# merch-hat.net
KiCad netlist of a schematic drawn in EAGLE
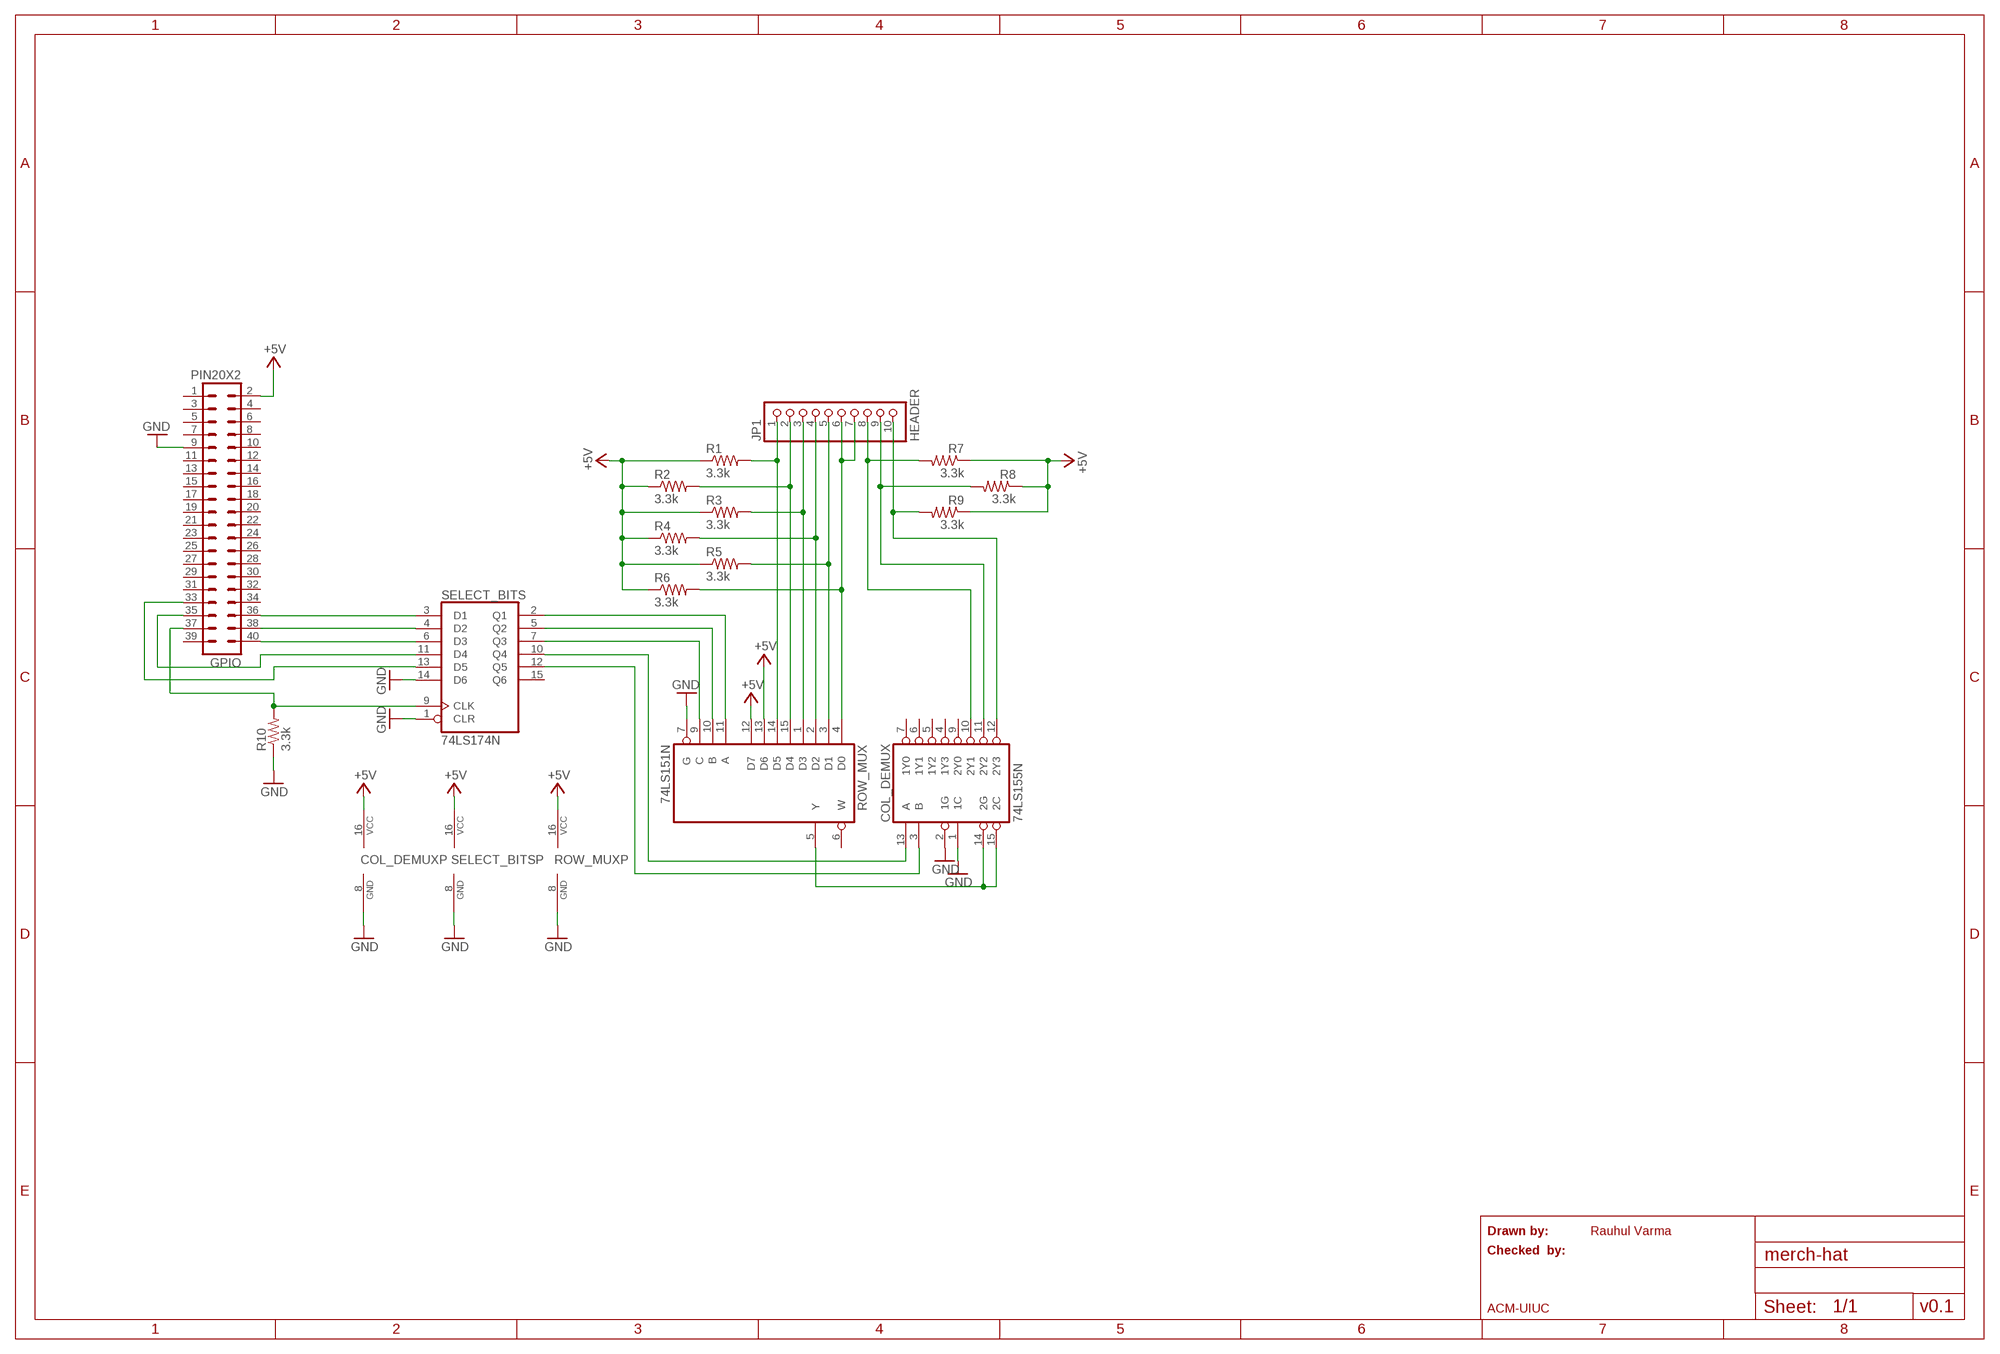
[diagram p0: schematic, sheet 1]

(export (version "E")
  (design (tool "Eeschema 10.0.6"))
  (components
    (comp (ref "COL_DEMUX")
      (value "74LS155N")
      (footprint "eagle-import:DIL16")
      (libsource (lib "eagle-import") (part "74155NLS"))
    )
    (comp (ref "GPIO")
      (value "PIN20X2")
      (footprint "eagle-import:PIN_20X2")
      (libsource (lib "eagle-import") (part "PIN20X2"))
    )
    (comp (ref "JP1")
      (value "HEADER")
      (footprint "eagle-import:1X10")
      (libsource (lib "eagle-import") (part "PINHD-1X10"))
    )
    (comp (ref "R1")
      (value "3.3k")
      (footprint "eagle-import:0207_10")
      (libsource (lib "eagle-import") (part "R-US_0207/10"))
    )
    (comp (ref "R2")
      (value "3.3k")
      (footprint "eagle-import:0207_10")
      (libsource (lib "eagle-import") (part "R-US_0207/10"))
    )
    (comp (ref "R3")
      (value "3.3k")
      (footprint "eagle-import:0207_10")
      (libsource (lib "eagle-import") (part "R-US_0207/10"))
    )
    (comp (ref "R4")
      (value "3.3k")
      (footprint "eagle-import:0207_10")
      (libsource (lib "eagle-import") (part "R-US_0207/10"))
    )
    (comp (ref "R5")
      (value "3.3k")
      (footprint "eagle-import:0207_10")
      (libsource (lib "eagle-import") (part "R-US_0207/10"))
    )
    (comp (ref "R6")
      (value "3.3k")
      (footprint "eagle-import:0207_10")
      (libsource (lib "eagle-import") (part "R-US_0207/10"))
    )
    (comp (ref "R7")
      (value "3.3k")
      (footprint "eagle-import:0207_10")
      (libsource (lib "eagle-import") (part "R-US_0207/10"))
    )
    (comp (ref "R8")
      (value "3.3k")
      (footprint "eagle-import:0207_10")
      (libsource (lib "eagle-import") (part "R-US_0207/10"))
    )
    (comp (ref "R9")
      (value "3.3k")
      (footprint "eagle-import:0207_10")
      (libsource (lib "eagle-import") (part "R-US_0207/10"))
    )
    (comp (ref "R10")
      (value "3.3k")
      (footprint "eagle-import:0207_10")
      (libsource (lib "eagle-import") (part "R-US_0207/10"))
    )
    (comp (ref "ROW_MUX")
      (value "74LS151N")
      (footprint "eagle-import:DIL16")
      (libsource (lib "eagle-import") (part "74151NLS"))
    )
    (comp (ref "SELECT_BITS")
      (value "74LS174N")
      (footprint "eagle-import:DIL16")
      (libsource (lib "eagle-import") (part "74174NLS"))
    )
  )
  (nets
    (net (code "1") (name "+5V") (class "Default")
      (node (ref "COL_DEMUX") (pin "16") (pinfunction "VCC_16") (pintype "power_in"))
      (node (ref "GPIO") (pin "2") (pinfunction "2_2") (pintype "passive"))
      (node (ref "R1") (pin "1") (pinfunction "1_1") (pintype "passive"))
      (node (ref "R2") (pin "1") (pinfunction "1_1") (pintype "passive"))
      (node (ref "R3") (pin "1") (pinfunction "1_1") (pintype "passive"))
      (node (ref "R4") (pin "1") (pinfunction "1_1") (pintype "passive"))
      (node (ref "R5") (pin "1") (pinfunction "1_1") (pintype "passive"))
      (node (ref "R6") (pin "1") (pinfunction "1_1") (pintype "passive"))
      (node (ref "R7") (pin "1") (pinfunction "1_1") (pintype "passive"))
      (node (ref "R8") (pin "1") (pinfunction "1_1") (pintype "passive"))
      (node (ref "R9") (pin "1") (pinfunction "1_1") (pintype "passive"))
      (node (ref "ROW_MUX") (pin "12") (pinfunction "D7_12") (pintype "input"))
      (node (ref "ROW_MUX") (pin "13") (pinfunction "D6_13") (pintype "input"))
      (node (ref "ROW_MUX") (pin "16") (pinfunction "VCC_16") (pintype "power_in"))
      (node (ref "SELECT_BITS") (pin "16") (pinfunction "VCC_16") (pintype "power_in"))
    )
    (net (code "2") (name "GND") (class "Default")
      (node (ref "COL_DEMUX") (pin "1") (pinfunction "1C_1") (pintype "input"))
      (node (ref "COL_DEMUX") (pin "2") (pinfunction "1G_2") (pintype "input"))
      (node (ref "COL_DEMUX") (pin "8") (pinfunction "GND_8") (pintype "power_in"))
      (node (ref "GPIO") (pin "9") (pinfunction "9_9") (pintype "passive"))
      (node (ref "R10") (pin "1") (pinfunction "1_1") (pintype "passive"))
      (node (ref "ROW_MUX") (pin "7") (pinfunction "G_7") (pintype "input"))
      (node (ref "ROW_MUX") (pin "8") (pinfunction "GND_8") (pintype "power_in"))
      (node (ref "SELECT_BITS") (pin "1") (pinfunction "CLR_1") (pintype "input"))
      (node (ref "SELECT_BITS") (pin "14") (pinfunction "D6_14") (pintype "input"))
      (node (ref "SELECT_BITS") (pin "8") (pinfunction "GND_8") (pintype "power_in"))
    )
    (net (code "3") (name "Net-(COL_DEMUXA-2C)") (class "Default")
      (node (ref "COL_DEMUX") (pin "14") (pinfunction "2G_14") (pintype "input"))
      (node (ref "COL_DEMUX") (pin "15") (pinfunction "2C_15") (pintype "input"))
      (node (ref "ROW_MUX") (pin "5") (pinfunction "Y_5") (pintype "output"))
    )
    (net (code "4") (name "Net-(COL_DEMUXA-2Y1)") (class "Default")
      (node (ref "COL_DEMUX") (pin "10") (pinfunction "2Y1_10") (pintype "output"))
      (node (ref "JP1") (pin "8") (pinfunction "8_8") (pintype "passive"))
      (node (ref "R7") (pin "2") (pinfunction "2_2") (pintype "passive"))
    )
    (net (code "5") (name "Net-(COL_DEMUXA-2Y2)") (class "Default")
      (node (ref "COL_DEMUX") (pin "11") (pinfunction "2Y2_11") (pintype "output"))
      (node (ref "JP1") (pin "9") (pinfunction "9_9") (pintype "passive"))
      (node (ref "R8") (pin "2") (pinfunction "2_2") (pintype "passive"))
    )
    (net (code "6") (name "Net-(COL_DEMUXA-2Y3)") (class "Default")
      (node (ref "COL_DEMUX") (pin "12") (pinfunction "2Y3_12") (pintype "output"))
      (node (ref "JP1") (pin "10") (pinfunction "10_10") (pintype "passive"))
      (node (ref "R9") (pin "2") (pinfunction "2_2") (pintype "passive"))
    )
    (net (code "7") (name "Net-(COL_DEMUXA-A)") (class "Default")
      (node (ref "COL_DEMUX") (pin "13") (pinfunction "A_13") (pintype "input"))
      (node (ref "SELECT_BITS") (pin "10") (pinfunction "Q4_10") (pintype "output"))
    )
    (net (code "8") (name "Net-(COL_DEMUXA-B)") (class "Default")
      (node (ref "COL_DEMUX") (pin "3") (pinfunction "B_3") (pintype "input"))
      (node (ref "SELECT_BITS") (pin "12") (pinfunction "Q5_12") (pintype "output"))
    )
    (net (code "9") (name "Net-(ROW_MUXA-A)") (class "Default")
      (node (ref "ROW_MUX") (pin "11") (pinfunction "A_11") (pintype "input"))
      (node (ref "SELECT_BITS") (pin "2") (pinfunction "Q1_2") (pintype "output"))
    )
    (net (code "10") (name "Net-(ROW_MUXA-B)") (class "Default")
      (node (ref "ROW_MUX") (pin "10") (pinfunction "B_10") (pintype "input"))
      (node (ref "SELECT_BITS") (pin "5") (pinfunction "Q2_5") (pintype "output"))
    )
    (net (code "11") (name "Net-(ROW_MUXA-C)") (class "Default")
      (node (ref "ROW_MUX") (pin "9") (pinfunction "C_9") (pintype "input"))
      (node (ref "SELECT_BITS") (pin "7") (pinfunction "Q3_7") (pintype "output"))
    )
    (net (code "12") (name "Net-(ROW_MUXA-D0)") (class "Default")
      (node (ref "JP1") (pin "6") (pinfunction "6_6") (pintype "passive"))
      (node (ref "JP1") (pin "7") (pinfunction "7_7") (pintype "passive"))
      (node (ref "R6") (pin "2") (pinfunction "2_2") (pintype "passive"))
      (node (ref "ROW_MUX") (pin "4") (pinfunction "D0_4") (pintype "input"))
    )
    (net (code "13") (name "Net-(ROW_MUXA-D1)") (class "Default")
      (node (ref "JP1") (pin "5") (pinfunction "5_5") (pintype "passive"))
      (node (ref "R5") (pin "2") (pinfunction "2_2") (pintype "passive"))
      (node (ref "ROW_MUX") (pin "3") (pinfunction "D1_3") (pintype "input"))
    )
    (net (code "14") (name "Net-(ROW_MUXA-D2)") (class "Default")
      (node (ref "JP1") (pin "4") (pinfunction "4_4") (pintype "passive"))
      (node (ref "R4") (pin "2") (pinfunction "2_2") (pintype "passive"))
      (node (ref "ROW_MUX") (pin "2") (pinfunction "D2_2") (pintype "input"))
    )
    (net (code "15") (name "Net-(ROW_MUXA-D3)") (class "Default")
      (node (ref "JP1") (pin "3") (pinfunction "3_3") (pintype "passive"))
      (node (ref "R3") (pin "2") (pinfunction "2_2") (pintype "passive"))
      (node (ref "ROW_MUX") (pin "1") (pinfunction "D3_1") (pintype "input"))
    )
    (net (code "16") (name "Net-(ROW_MUXA-D4)") (class "Default")
      (node (ref "JP1") (pin "2") (pinfunction "2_2") (pintype "passive"))
      (node (ref "R2") (pin "2") (pinfunction "2_2") (pintype "passive"))
      (node (ref "ROW_MUX") (pin "15") (pinfunction "D4_15") (pintype "input"))
    )
    (net (code "17") (name "Net-(ROW_MUXA-D5)") (class "Default")
      (node (ref "JP1") (pin "1") (pinfunction "1_1") (pintype "passive"))
      (node (ref "R1") (pin "2") (pinfunction "2_2") (pintype "passive"))
      (node (ref "ROW_MUX") (pin "14") (pinfunction "D5_14") (pintype "input"))
    )
    (net (code "18") (name "Net-(SELECT_BITSA-CLK)") (class "Default")
      (node (ref "GPIO") (pin "37") (pinfunction "37_37") (pintype "passive"))
      (node (ref "R10") (pin "2") (pinfunction "2_2") (pintype "passive"))
      (node (ref "SELECT_BITS") (pin "9") (pinfunction "CLK_9") (pintype "input"))
    )
    (net (code "19") (name "Net-(SELECT_BITSA-D1)") (class "Default")
      (node (ref "GPIO") (pin "36") (pinfunction "36_36") (pintype "passive"))
      (node (ref "SELECT_BITS") (pin "3") (pinfunction "D1_3") (pintype "input"))
    )
    (net (code "20") (name "Net-(SELECT_BITSA-D2)") (class "Default")
      (node (ref "GPIO") (pin "38") (pinfunction "38_38") (pintype "passive"))
      (node (ref "SELECT_BITS") (pin "4") (pinfunction "D2_4") (pintype "input"))
    )
    (net (code "21") (name "Net-(SELECT_BITSA-D3)") (class "Default")
      (node (ref "GPIO") (pin "40") (pinfunction "40_40") (pintype "passive"))
      (node (ref "SELECT_BITS") (pin "6") (pinfunction "D3_6") (pintype "input"))
    )
    (net (code "22") (name "Net-(SELECT_BITSA-D4)") (class "Default")
      (node (ref "GPIO") (pin "35") (pinfunction "35_35") (pintype "passive"))
      (node (ref "SELECT_BITS") (pin "11") (pinfunction "D4_11") (pintype "input"))
    )
    (net (code "23") (name "Net-(SELECT_BITSA-D5)") (class "Default")
      (node (ref "GPIO") (pin "33") (pinfunction "33_33") (pintype "passive"))
      (node (ref "SELECT_BITS") (pin "13") (pinfunction "D5_13") (pintype "input"))
    )
    (net (code "24") (name "unconnected-(COL_DEMUXA-1Y0-Pad7)") (class "Default")
      (node (ref "COL_DEMUX") (pin "7") (pinfunction "1Y0_7") (pintype "output"))
    )
    (net (code "25") (name "unconnected-(COL_DEMUXA-1Y1-Pad6)") (class "Default")
      (node (ref "COL_DEMUX") (pin "6") (pinfunction "1Y1_6") (pintype "output"))
    )
    (net (code "26") (name "unconnected-(COL_DEMUXA-1Y2-Pad5)") (class "Default")
      (node (ref "COL_DEMUX") (pin "5") (pinfunction "1Y2_5") (pintype "output"))
    )
    (net (code "27") (name "unconnected-(COL_DEMUXA-1Y3-Pad4)") (class "Default")
      (node (ref "COL_DEMUX") (pin "4") (pinfunction "1Y3_4") (pintype "output"))
    )
    (net (code "28") (name "unconnected-(COL_DEMUXA-2Y0-Pad9)") (class "Default")
      (node (ref "COL_DEMUX") (pin "9") (pinfunction "2Y0_9") (pintype "output"))
    )
    (net (code "29") (name "unconnected-(GPIO-Pad1)") (class "Default")
      (node (ref "GPIO") (pin "1") (pinfunction "1_1") (pintype "passive"))
    )
    (net (code "30") (name "unconnected-(GPIO-Pad3)") (class "Default")
      (node (ref "GPIO") (pin "3") (pinfunction "3_3") (pintype "passive"))
    )
    (net (code "31") (name "unconnected-(GPIO-Pad4)") (class "Default")
      (node (ref "GPIO") (pin "4") (pinfunction "4_4") (pintype "passive"))
    )
    (net (code "32") (name "unconnected-(GPIO-Pad5)") (class "Default")
      (node (ref "GPIO") (pin "5") (pinfunction "5_5") (pintype "passive"))
    )
    (net (code "33") (name "unconnected-(GPIO-Pad6)") (class "Default")
      (node (ref "GPIO") (pin "6") (pinfunction "6_6") (pintype "passive"))
    )
    (net (code "34") (name "unconnected-(GPIO-Pad7)") (class "Default")
      (node (ref "GPIO") (pin "7") (pinfunction "7_7") (pintype "passive"))
    )
    (net (code "35") (name "unconnected-(GPIO-Pad8)") (class "Default")
      (node (ref "GPIO") (pin "8") (pinfunction "8_8") (pintype "passive"))
    )
    (net (code "36") (name "unconnected-(GPIO-Pad10)") (class "Default")
      (node (ref "GPIO") (pin "10") (pinfunction "10_10") (pintype "passive"))
    )
    (net (code "37") (name "unconnected-(GPIO-Pad11)") (class "Default")
      (node (ref "GPIO") (pin "11") (pinfunction "11_11") (pintype "passive"))
    )
    (net (code "38") (name "unconnected-(GPIO-Pad12)") (class "Default")
      (node (ref "GPIO") (pin "12") (pinfunction "12_12") (pintype "passive"))
    )
    (net (code "39") (name "unconnected-(GPIO-Pad13)") (class "Default")
      (node (ref "GPIO") (pin "13") (pinfunction "13_13") (pintype "passive"))
    )
    (net (code "40") (name "unconnected-(GPIO-Pad14)") (class "Default")
      (node (ref "GPIO") (pin "14") (pinfunction "14_14") (pintype "passive"))
    )
    (net (code "41") (name "unconnected-(GPIO-Pad15)") (class "Default")
      (node (ref "GPIO") (pin "15") (pinfunction "15_15") (pintype "passive"))
    )
    (net (code "42") (name "unconnected-(GPIO-Pad16)") (class "Default")
      (node (ref "GPIO") (pin "16") (pinfunction "16_16") (pintype "passive"))
    )
    (net (code "43") (name "unconnected-(GPIO-Pad17)") (class "Default")
      (node (ref "GPIO") (pin "17") (pinfunction "17_17") (pintype "passive"))
    )
    (net (code "44") (name "unconnected-(GPIO-Pad18)") (class "Default")
      (node (ref "GPIO") (pin "18") (pinfunction "18_18") (pintype "passive"))
    )
    (net (code "45") (name "unconnected-(GPIO-Pad19)") (class "Default")
      (node (ref "GPIO") (pin "19") (pinfunction "19_19") (pintype "passive"))
    )
    (net (code "46") (name "unconnected-(GPIO-Pad20)") (class "Default")
      (node (ref "GPIO") (pin "20") (pinfunction "20_20") (pintype "passive"))
    )
    (net (code "47") (name "unconnected-(GPIO-Pad21)") (class "Default")
      (node (ref "GPIO") (pin "21") (pinfunction "21_21") (pintype "passive"))
    )
    (net (code "48") (name "unconnected-(GPIO-Pad22)") (class "Default")
      (node (ref "GPIO") (pin "22") (pinfunction "22_22") (pintype "passive"))
    )
    (net (code "49") (name "unconnected-(GPIO-Pad23)") (class "Default")
      (node (ref "GPIO") (pin "23") (pinfunction "23_23") (pintype "passive"))
    )
    (net (code "50") (name "unconnected-(GPIO-Pad24)") (class "Default")
      (node (ref "GPIO") (pin "24") (pinfunction "24_24") (pintype "passive"))
    )
    (net (code "51") (name "unconnected-(GPIO-Pad25)") (class "Default")
      (node (ref "GPIO") (pin "25") (pinfunction "25_25") (pintype "passive"))
    )
    (net (code "52") (name "unconnected-(GPIO-Pad26)") (class "Default")
      (node (ref "GPIO") (pin "26") (pinfunction "26_26") (pintype "passive"))
    )
    (net (code "53") (name "unconnected-(GPIO-Pad27)") (class "Default")
      (node (ref "GPIO") (pin "27") (pinfunction "27_27") (pintype "passive"))
    )
    (net (code "54") (name "unconnected-(GPIO-Pad28)") (class "Default")
      (node (ref "GPIO") (pin "28") (pinfunction "28_28") (pintype "passive"))
    )
    (net (code "55") (name "unconnected-(GPIO-Pad29)") (class "Default")
      (node (ref "GPIO") (pin "29") (pinfunction "29_29") (pintype "passive"))
    )
    (net (code "56") (name "unconnected-(GPIO-Pad30)") (class "Default")
      (node (ref "GPIO") (pin "30") (pinfunction "30_30") (pintype "passive"))
    )
    (net (code "57") (name "unconnected-(GPIO-Pad31)") (class "Default")
      (node (ref "GPIO") (pin "31") (pinfunction "31_31") (pintype "passive"))
    )
    (net (code "58") (name "unconnected-(GPIO-Pad32)") (class "Default")
      (node (ref "GPIO") (pin "32") (pinfunction "32_32") (pintype "passive"))
    )
    (net (code "59") (name "unconnected-(GPIO-Pad34)") (class "Default")
      (node (ref "GPIO") (pin "34") (pinfunction "34_34") (pintype "passive"))
    )
    (net (code "60") (name "unconnected-(GPIO-Pad39)") (class "Default")
      (node (ref "GPIO") (pin "39") (pinfunction "39_39") (pintype "passive"))
    )
    (net (code "61") (name "unconnected-(ROW_MUXA-W-Pad6)") (class "Default")
      (node (ref "ROW_MUX") (pin "6") (pinfunction "W_6") (pintype "output"))
    )
    (net (code "62") (name "unconnected-(SELECT_BITSA-Q6-Pad15)") (class "Default")
      (node (ref "SELECT_BITS") (pin "15") (pinfunction "Q6_15") (pintype "output"))
    )
  )
)
